# schematicamitfix.net
KiCad netlist of a schematic drawn in EAGLE
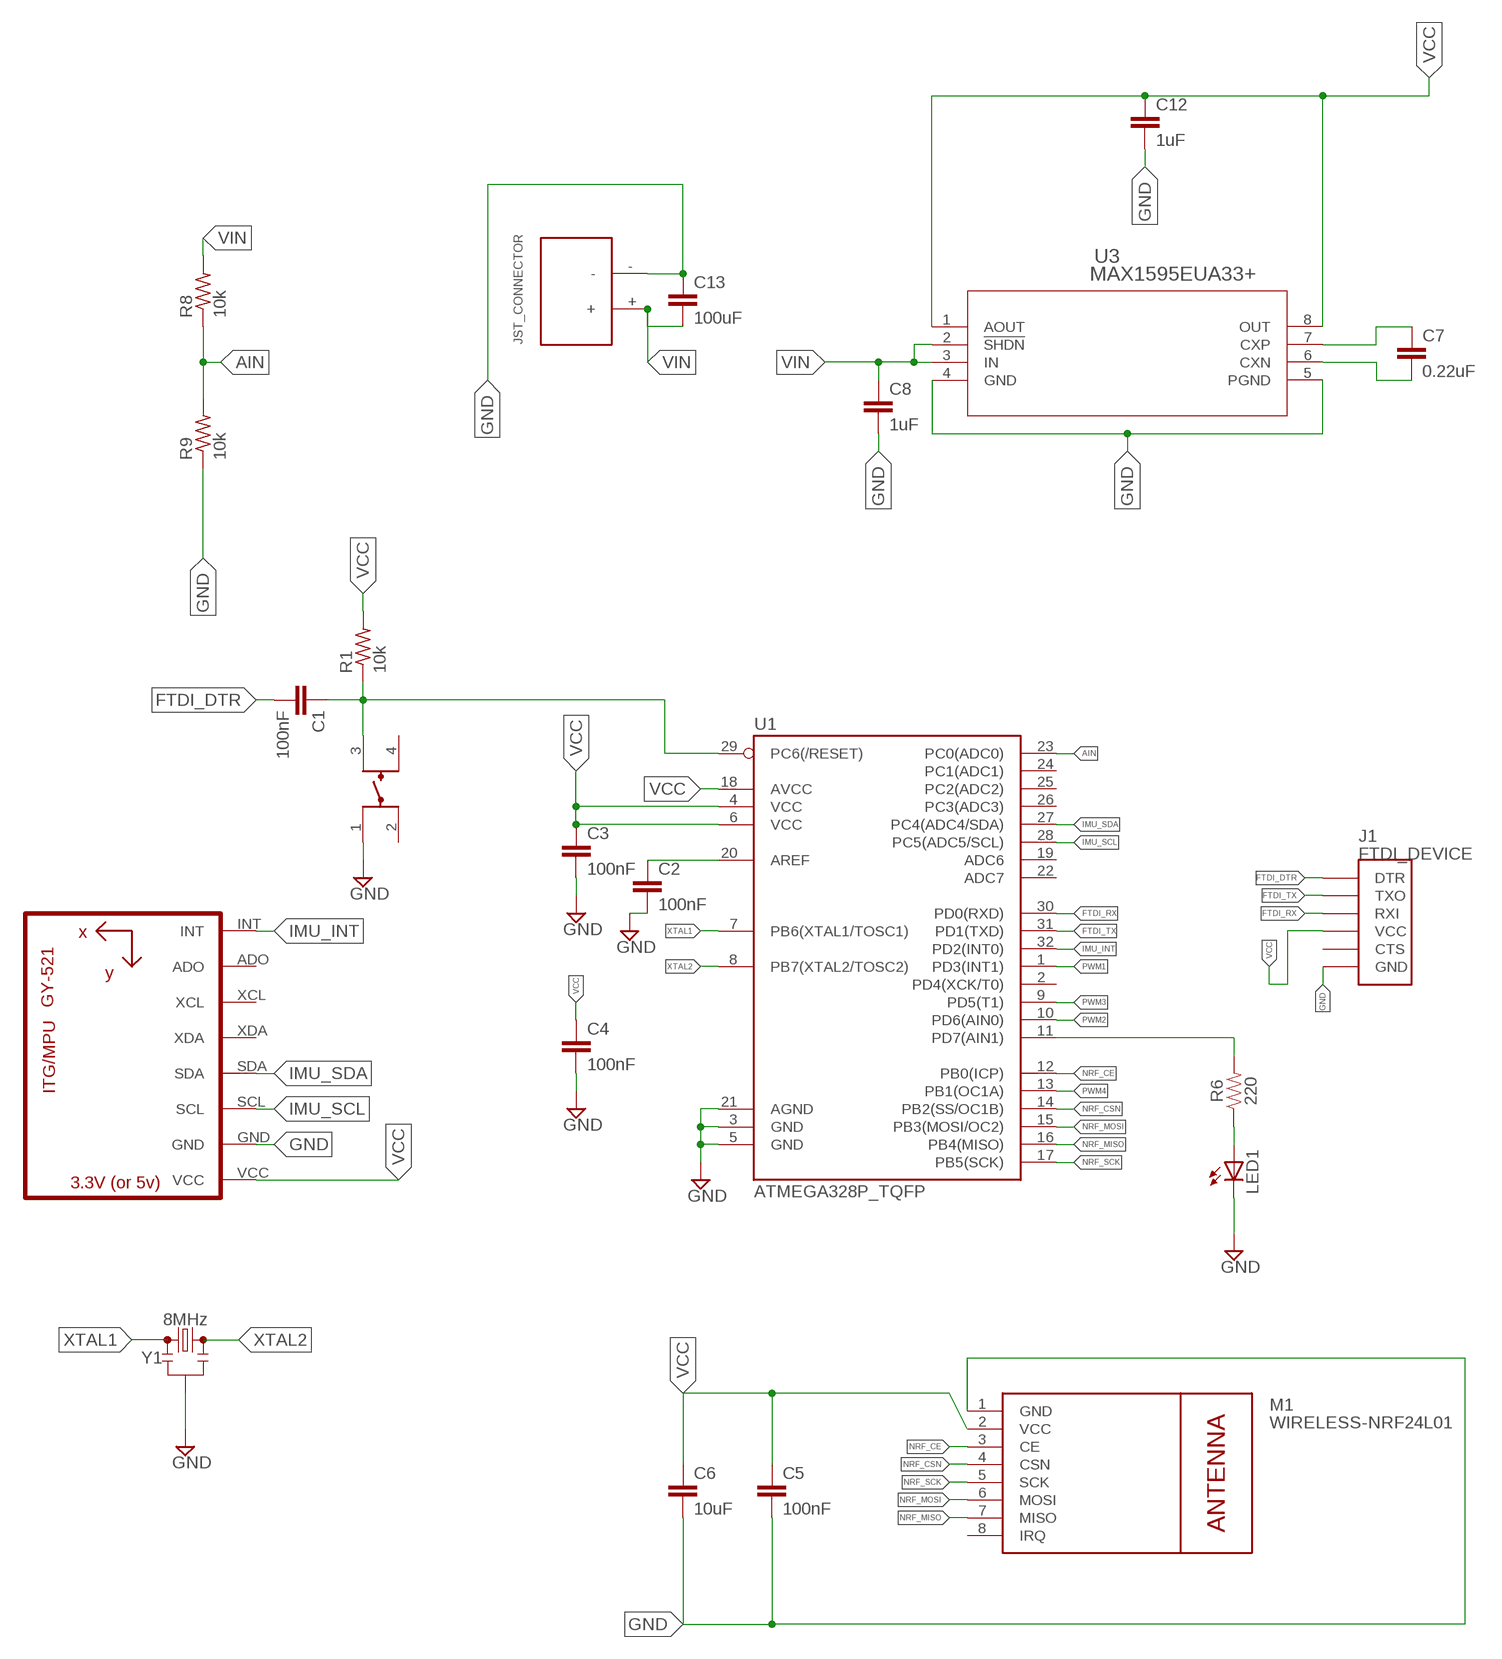
[diagram p0: schematic, sheet 1, part 1 of 3]
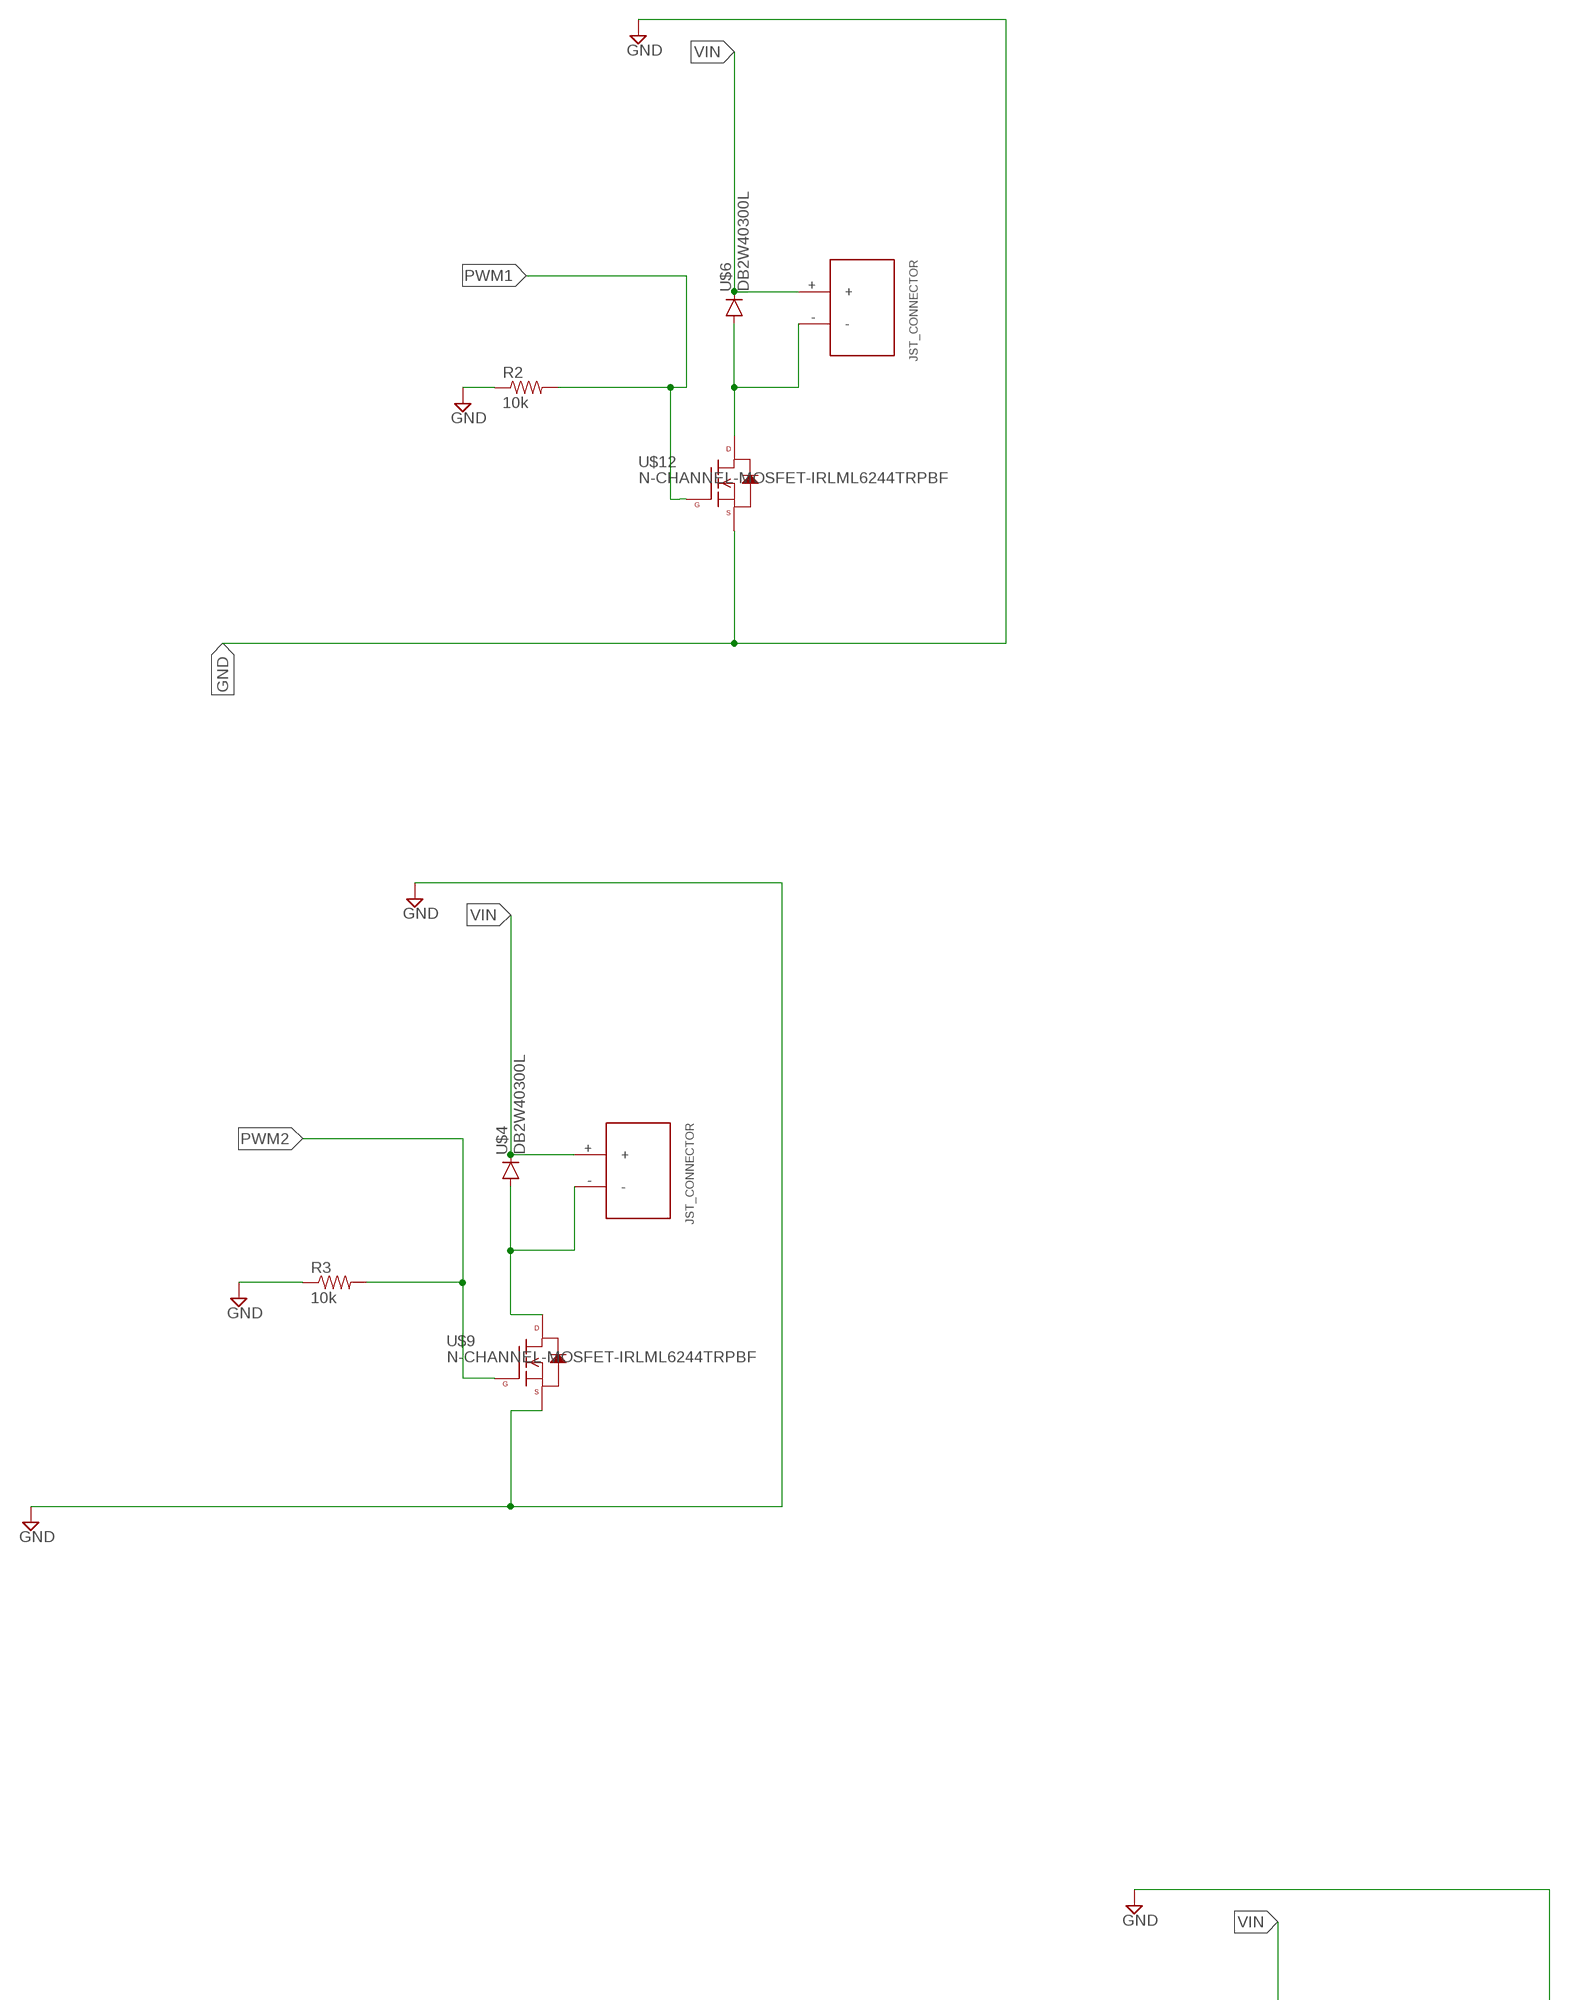
[diagram p1: schematic, sheet 1, part 2 of 3]
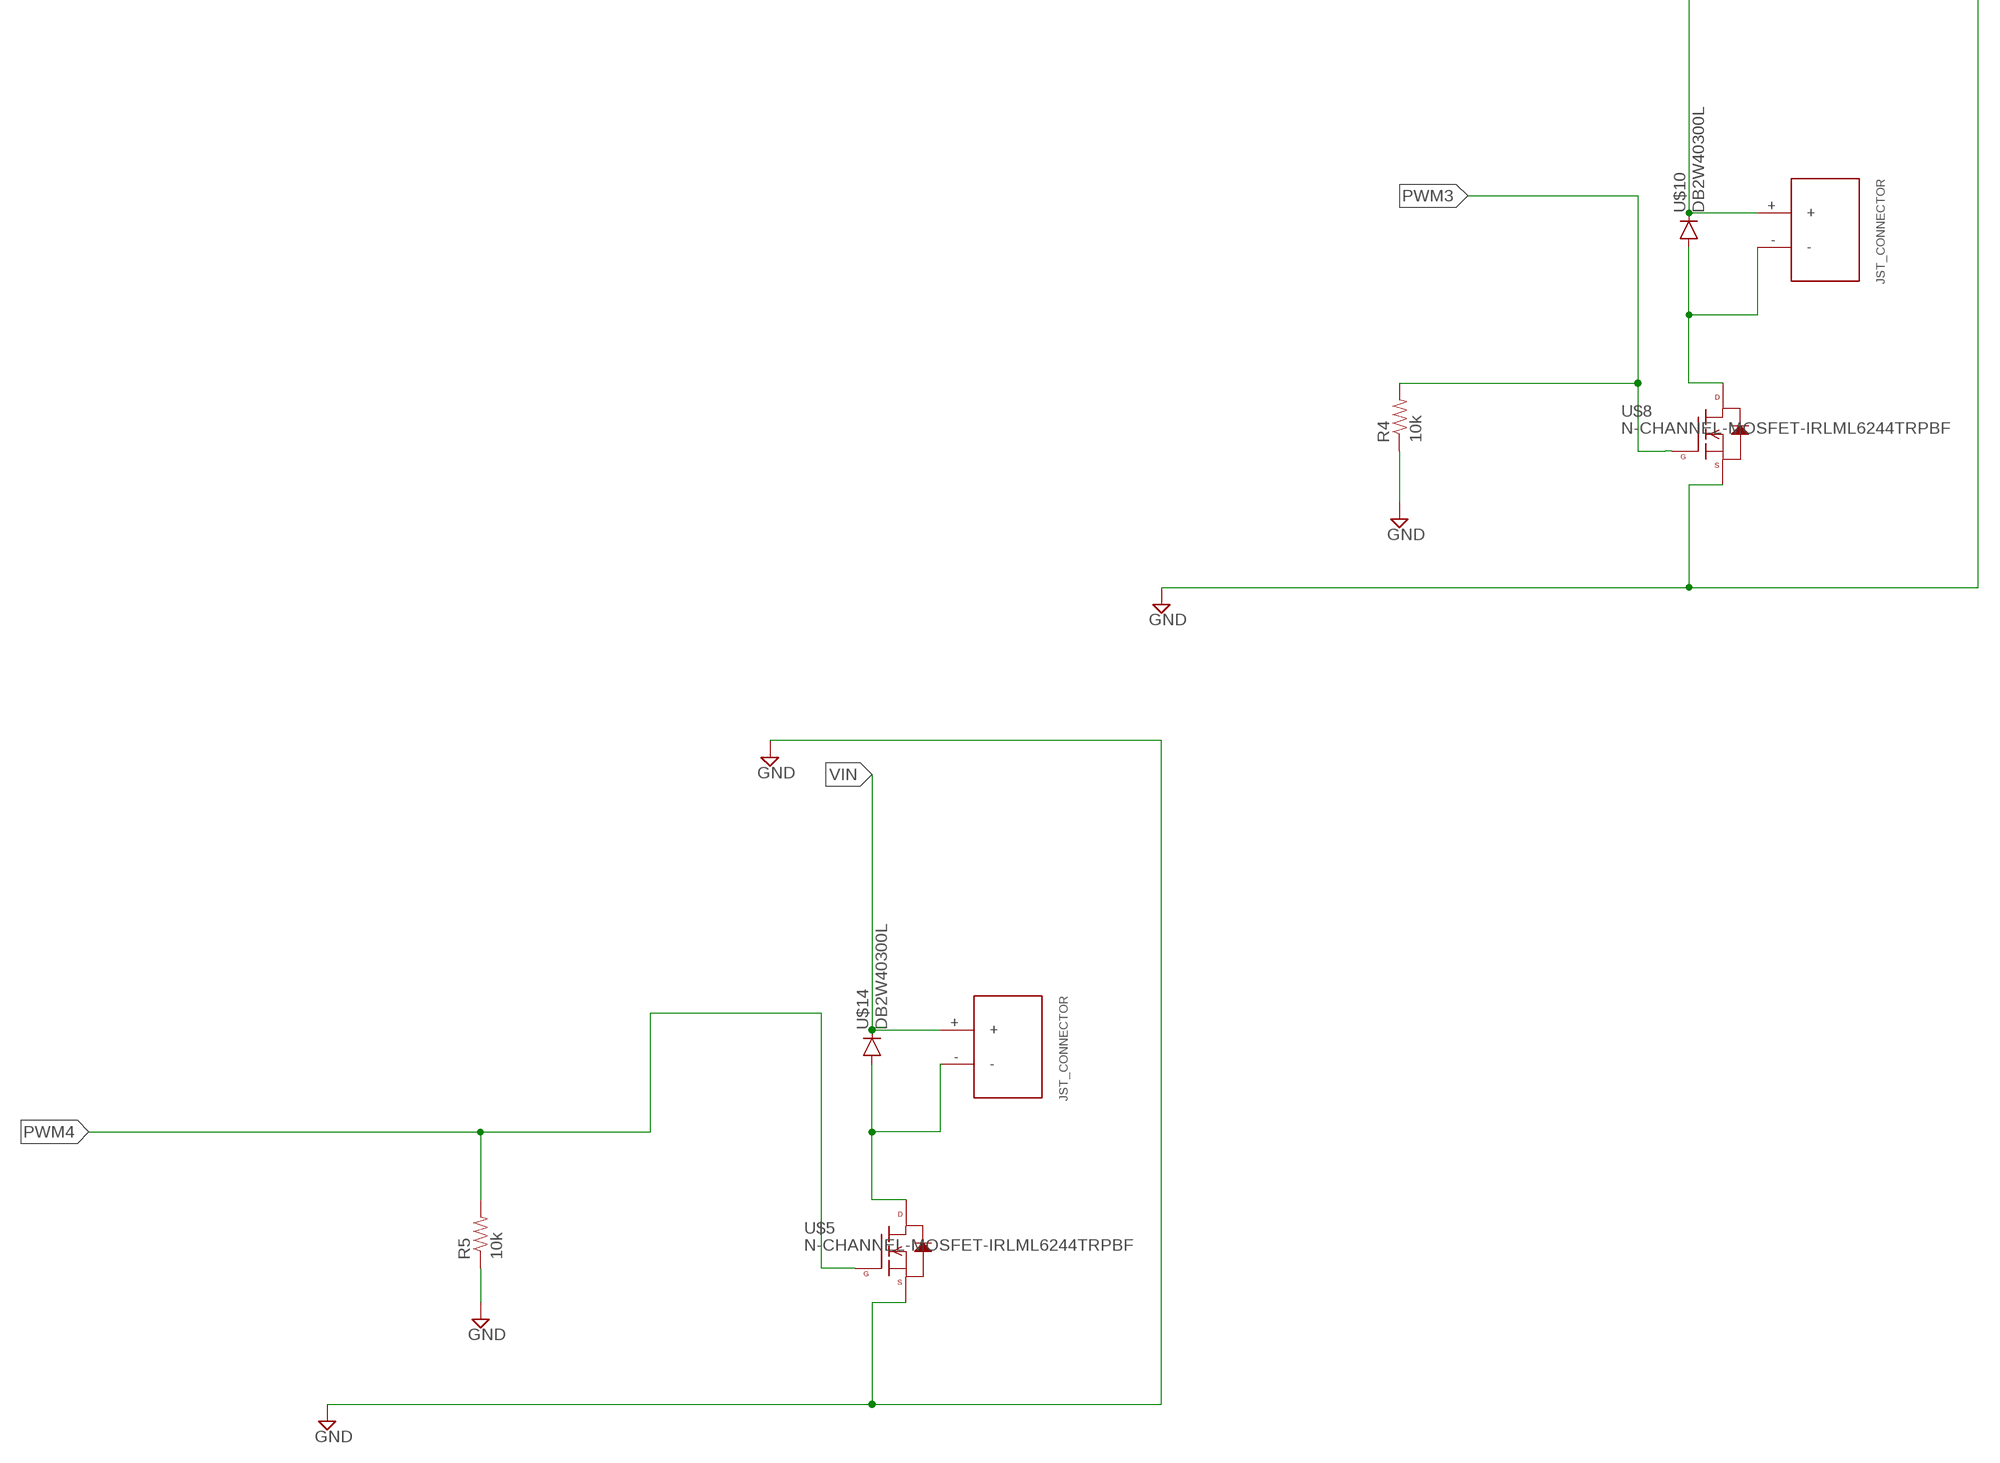
[diagram p2: schematic, sheet 1, part 3 of 3]

(export (version "E")
  (design (tool "Eeschema 10.0.6"))
  (components
    (comp (ref "C1")
      (value "100nF")
      (footprint "eagle-import:C0603")
      (libsource (lib "eagle-import") (part "C-EUC0603"))
    )
    (comp (ref "C2")
      (value "100nF")
      (footprint "eagle-import:C0603")
      (libsource (lib "eagle-import") (part "C-EUC0603"))
    )
    (comp (ref "C3")
      (value "100nF")
      (footprint "eagle-import:C0603")
      (libsource (lib "eagle-import") (part "C-EUC0603"))
    )
    (comp (ref "C4")
      (value "100nF")
      (footprint "eagle-import:C0603")
      (libsource (lib "eagle-import") (part "C-EUC0603"))
    )
    (comp (ref "C5")
      (value "100nF")
      (footprint "eagle-import:C0603")
      (libsource (lib "eagle-import") (part "C-EUC0603"))
    )
    (comp (ref "C6")
      (value "10uF")
      (footprint "eagle-import:C0603")
      (libsource (lib "eagle-import") (part "C-EUC0603"))
    )
    (comp (ref "C7")
      (value "0.22uF")
      (footprint "eagle-import:C0603")
      (libsource (lib "eagle-import") (part "C-EUC0603"))
    )
    (comp (ref "C8")
      (value "1uF")
      (footprint "eagle-import:C0805")
      (libsource (lib "eagle-import") (part "C-EUC0805"))
    )
    (comp (ref "C12")
      (value "1uF")
      (footprint "eagle-import:C0805")
      (libsource (lib "eagle-import") (part "C-EUC0805"))
    )
    (comp (ref "C13")
      (value "100uF")
      (footprint "eagle-import:C1210")
      (libsource (lib "eagle-import") (part "C-EUC1210"))
    )
    (comp (ref "J1")
      (value "FTDI_DEVICE")
      (footprint "eagle-import:FTDI_DEVICE_SIDE")
      (libsource (lib "eagle-import") (part "FTDI_DEVICE"))
    )
    (comp (ref "LED1")
      (value "LED1206")
      (footprint "eagle-import:LED-1206")
      (libsource (lib "eagle-import") (part "LED1206"))
    )
    (comp (ref "M1")
      (value "WIRELESS-NRF24L01")
      (footprint "eagle-import:WIRELESS-NRF24L01")
      (libsource (lib "eagle-import") (part "WIRELESS-NRF24L01"))
    )
    (comp (ref "R1")
      (value "10k")
      (footprint "eagle-import:R0603")
      (libsource (lib "eagle-import") (part "R-US_R0603"))
    )
    (comp (ref "R2")
      (value "10k")
      (footprint "eagle-import:0603-RES")
      (libsource (lib "eagle-import") (part "RESISTOR0603"))
    )
    (comp (ref "R3")
      (value "10k")
      (footprint "eagle-import:0603-RES")
      (libsource (lib "eagle-import") (part "RESISTOR0603"))
    )
    (comp (ref "R4")
      (value "10k")
      (footprint "eagle-import:0603-RES")
      (libsource (lib "eagle-import") (part "RESISTOR0603"))
    )
    (comp (ref "R5")
      (value "10k")
      (footprint "eagle-import:0603-RES")
      (libsource (lib "eagle-import") (part "RESISTOR0603"))
    )
    (comp (ref "R6")
      (value "220")
      (footprint "eagle-import:0603")
      (libsource (lib "eagle-import") (part "220OHM-0603-1/10W-1%"))
    )
    (comp (ref "R8")
      (value "10k")
      (footprint "eagle-import:R0603")
      (libsource (lib "eagle-import") (part "R-US_R0603"))
    )
    (comp (ref "R9")
      (value "10k")
      (footprint "eagle-import:R0603")
      (libsource (lib "eagle-import") (part "R-US_R0603"))
    )
    (comp (ref "U$1")
      (value "LL3301NF065QG")
      (footprint "eagle-import:LL3301NF065QG")
      (libsource (lib "eagle-import") (part "LL3301NF065QG"))
    )
    (comp (ref "U$3")
      (value "JST_CONNECTOR_FEMALE")
      (footprint "eagle-import:JST_CONNECTOR_FEMALE")
      (libsource (lib "eagle-import") (part "JST_CONNECTOR_FEMALE"))
    )
    (comp (ref "U$4")
      (value "DB2W40300L")
      (footprint "eagle-import:MINI2-F3-B")
      (libsource (lib "eagle-import") (part "DB2W40300L"))
    )
    (comp (ref "U$5")
      (value "N-CHANNEL-MOSFET-IRLML6244TRPBF")
      (footprint "eagle-import:SOT23-3")
      (libsource (lib "eagle-import") (part "N-CHANNEL-MOSFET-IRLML6244TRPBF"))
    )
    (comp (ref "U$6")
      (value "DB2W40300L")
      (footprint "eagle-import:MINI2-F3-B")
      (libsource (lib "eagle-import") (part "DB2W40300L"))
    )
    (comp (ref "U$7")
      (value "JST_CONNECTOR_FEMALE")
      (footprint "eagle-import:JST_CONNECTOR_FEMALE")
      (libsource (lib "eagle-import") (part "JST_CONNECTOR_FEMALE"))
    )
    (comp (ref "U$8")
      (value "N-CHANNEL-MOSFET-IRLML6244TRPBF")
      (footprint "eagle-import:SOT23-3")
      (libsource (lib "eagle-import") (part "N-CHANNEL-MOSFET-IRLML6244TRPBF"))
    )
    (comp (ref "U$9")
      (value "N-CHANNEL-MOSFET-IRLML6244TRPBF")
      (footprint "eagle-import:SOT23-3")
      (libsource (lib "eagle-import") (part "N-CHANNEL-MOSFET-IRLML6244TRPBF"))
    )
    (comp (ref "U$10")
      (value "DB2W40300L")
      (footprint "eagle-import:MINI2-F3-B")
      (libsource (lib "eagle-import") (part "DB2W40300L"))
    )
    (comp (ref "U$11")
      (value "JST_CONNECTOR_FEMALE")
      (footprint "eagle-import:JST_CONNECTOR_FEMALE")
      (libsource (lib "eagle-import") (part "JST_CONNECTOR_FEMALE"))
    )
    (comp (ref "U$12")
      (value "N-CHANNEL-MOSFET-IRLML6244TRPBF")
      (footprint "eagle-import:SOT23-3")
      (libsource (lib "eagle-import") (part "N-CHANNEL-MOSFET-IRLML6244TRPBF"))
    )
    (comp (ref "U$14")
      (value "DB2W40300L")
      (footprint "eagle-import:MINI2-F3-B")
      (libsource (lib "eagle-import") (part "DB2W40300L"))
    )
    (comp (ref "U$15")
      (value "JST_CONNECTOR_FEMALE")
      (footprint "eagle-import:JST_CONNECTOR_FEMALE")
      (libsource (lib "eagle-import") (part "JST_CONNECTOR_FEMALE"))
    )
    (comp (ref "U$19")
      (value "JST_CONNECTOR_FEMALE")
      (footprint "eagle-import:JST_CONNECTOR_FEMALE")
      (libsource (lib "eagle-import") (part "JST_CONNECTOR_FEMALE"))
    )
    (comp (ref "U1")
      (value "ATMEGA328P_TQFP")
      (footprint "eagle-import:TQFP32-08")
      (libsource (lib "eagle-import") (part "ATMEGA328P_TQFP"))
    )
    (comp (ref "U2")
      (value "GY-521MPU6050")
      (footprint "eagle-import:GY-521")
      (libsource (lib "eagle-import") (part "GY-521MPU6050"))
    )
    (comp (ref "U3")
      (value "MAX1595EUA33+")
      (footprint "eagle-import:21-0036K")
      (libsource (lib "eagle-import") (part "MAX1595EUA33+"))
    )
    (comp (ref "Y1")
      (value "8MHz")
      (footprint "eagle-import:RESONATOR-SMD-3.2X1.3")
      (libsource (lib "eagle-import") (part "RESONATOR-8MHZSMD_3.2X1.3"))
    )
  )
  (nets
    (net (code "1") (name "AIN") (class "Default")
      (node (ref "R8") (pin "1") (pinfunction "1_1") (pintype "passive"))
      (node (ref "R9") (pin "2") (pinfunction "2_2") (pintype "passive"))
      (node (ref "U1") (pin "23") (pinfunction "PC0(ADC0)_23") (pintype "bidirectional"))
    )
    (net (code "2") (name "FTDI_DTR") (class "Default")
      (node (ref "C1") (pin "2") (pinfunction "2_2") (pintype "passive"))
      (node (ref "J1") (pin "P$1") (pinfunction "DTR_P$1") (pintype "bidirectional"))
    )
    (net (code "3") (name "FTDI_RX") (class "Default")
      (node (ref "J1") (pin "P$3") (pinfunction "RXI_P$3") (pintype "bidirectional"))
      (node (ref "U1") (pin "30") (pinfunction "PD0(RXD)_30") (pintype "bidirectional"))
    )
    (net (code "4") (name "FTDI_TX") (class "Default")
      (node (ref "J1") (pin "P$2") (pinfunction "TXO_P$2") (pintype "bidirectional"))
      (node (ref "U1") (pin "31") (pinfunction "PD1(TXD)_31") (pintype "bidirectional"))
    )
    (net (code "5") (name "GND") (class "Default")
      (node (ref "C12") (pin "2") (pinfunction "2_2") (pintype "passive"))
      (node (ref "C13") (pin "1") (pinfunction "1_1") (pintype "passive"))
      (node (ref "C2") (pin "2") (pinfunction "2_2") (pintype "passive"))
      (node (ref "C3") (pin "2") (pinfunction "2_2") (pintype "passive"))
      (node (ref "C4") (pin "2") (pinfunction "2_2") (pintype "passive"))
      (node (ref "C5") (pin "2") (pinfunction "2_2") (pintype "passive"))
      (node (ref "C6") (pin "2") (pinfunction "2_2") (pintype "passive"))
      (node (ref "C8") (pin "2") (pinfunction "2_2") (pintype "passive"))
      (node (ref "J1") (pin "P$6") (pinfunction "GND_P$6") (pintype "bidirectional"))
      (node (ref "LED1") (pin "C") (pinfunction "C_C") (pintype "passive"))
      (node (ref "M1") (pin "1") (pinfunction "GND_1") (pintype "power_in"))
      (node (ref "R2") (pin "1") (pinfunction "1_1") (pintype "passive"))
      (node (ref "R3") (pin "1") (pinfunction "1_1") (pintype "passive"))
      (node (ref "R4") (pin "1") (pinfunction "1_1") (pintype "passive"))
      (node (ref "R5") (pin "1") (pinfunction "1_1") (pintype "passive"))
      (node (ref "R9") (pin "1") (pinfunction "1_1") (pintype "passive"))
      (node (ref "U$1") (pin "1") (pinfunction "1_1") (pintype "passive"))
      (node (ref "U$12") (pin "2") (pinfunction "S_2") (pintype "passive"))
      (node (ref "U$19") (pin "-") (pinfunction "-_-") (pintype "bidirectional"))
      (node (ref "U$5") (pin "2") (pinfunction "S_2") (pintype "passive"))
      (node (ref "U$8") (pin "2") (pinfunction "S_2") (pintype "passive"))
      (node (ref "U$9") (pin "2") (pinfunction "S_2") (pintype "passive"))
      (node (ref "U1") (pin "21") (pinfunction "AGND_21") (pintype "bidirectional"))
      (node (ref "U1") (pin "3") (pinfunction "GND_3") (pintype "bidirectional"))
      (node (ref "U1") (pin "5") (pinfunction "GND_5") (pintype "bidirectional"))
      (node (ref "U2") (pin "GND") (pinfunction "GND_GND") (pintype "bidirectional"))
      (node (ref "U3") (pin "4") (pinfunction "GND_4") (pintype "power_in"))
      (node (ref "U3") (pin "5") (pinfunction "PGND_5") (pintype "passive"))
      (node (ref "Y1") (pin "2") (pinfunction "2_2") (pintype "passive"))
    )
    (net (code "6") (name "IMU_INT") (class "Default")
      (node (ref "U1") (pin "32") (pinfunction "PD2(INT0)_32") (pintype "bidirectional"))
      (node (ref "U2") (pin "INT") (pinfunction "INT_INT") (pintype "bidirectional"))
    )
    (net (code "7") (name "IMU_SCL") (class "Default")
      (node (ref "U1") (pin "28") (pinfunction "PC5(ADC5/SCL)_28") (pintype "bidirectional"))
      (node (ref "U2") (pin "SCL") (pinfunction "SCL_SCL") (pintype "bidirectional"))
    )
    (net (code "8") (name "IMU_SDA") (class "Default")
      (node (ref "U1") (pin "27") (pinfunction "PC4(ADC4/SDA)_27") (pintype "bidirectional"))
      (node (ref "U2") (pin "SDA") (pinfunction "SDA_SDA") (pintype "bidirectional"))
    )
    (net (code "9") (name "NRF_CE") (class "Default")
      (node (ref "M1") (pin "3") (pinfunction "CE_3") (pintype "bidirectional"))
      (node (ref "U1") (pin "12") (pinfunction "PB0(ICP)_12") (pintype "bidirectional"))
    )
    (net (code "10") (name "NRF_CSN") (class "Default")
      (node (ref "M1") (pin "4") (pinfunction "CSN_4") (pintype "bidirectional"))
      (node (ref "U1") (pin "14") (pinfunction "PB2(SS/OC1B)_14") (pintype "bidirectional"))
    )
    (net (code "11") (name "NRF_MISO") (class "Default")
      (node (ref "M1") (pin "7") (pinfunction "MISO_7") (pintype "bidirectional"))
      (node (ref "U1") (pin "16") (pinfunction "PB4(MISO)_16") (pintype "bidirectional"))
    )
    (net (code "12") (name "NRF_MOSI") (class "Default")
      (node (ref "M1") (pin "6") (pinfunction "MOSI_6") (pintype "bidirectional"))
      (node (ref "U1") (pin "15") (pinfunction "PB3(MOSI/OC2)_15") (pintype "bidirectional"))
    )
    (net (code "13") (name "NRF_SCK") (class "Default")
      (node (ref "M1") (pin "5") (pinfunction "SCK_5") (pintype "bidirectional"))
      (node (ref "U1") (pin "17") (pinfunction "PB5(SCK)_17") (pintype "bidirectional"))
    )
    (net (code "14") (name "Net-(LED1-PadA)") (class "Default")
      (node (ref "LED1") (pin "A") (pinfunction "A_A") (pintype "passive"))
      (node (ref "R6") (pin "1") (pinfunction "1_1") (pintype "passive"))
    )
    (net (code "15") (name "Net-(U$4-PPIN)") (class "Default")
      (node (ref "U$3") (pin "-") (pinfunction "-_-") (pintype "bidirectional"))
      (node (ref "U$4") (pin "POS") (pinfunction "PPIN_POS") (pintype "passive"))
      (node (ref "U$9") (pin "3") (pinfunction "D_3") (pintype "passive"))
    )
    (net (code "16") (name "Net-(U$10-PPIN)") (class "Default")
      (node (ref "U$10") (pin "POS") (pinfunction "PPIN_POS") (pintype "passive"))
      (node (ref "U$11") (pin "-") (pinfunction "-_-") (pintype "bidirectional"))
      (node (ref "U$8") (pin "3") (pinfunction "D_3") (pintype "passive"))
    )
    (net (code "17") (name "Net-(U$12-D)") (class "Default")
      (node (ref "U$12") (pin "3") (pinfunction "D_3") (pintype "passive"))
      (node (ref "U$6") (pin "POS") (pinfunction "PPIN_POS") (pintype "passive"))
      (node (ref "U$7") (pin "-") (pinfunction "-_-") (pintype "bidirectional"))
    )
    (net (code "18") (name "Net-(U$14-PPIN)") (class "Default")
      (node (ref "U$14") (pin "POS") (pinfunction "PPIN_POS") (pintype "passive"))
      (node (ref "U$15") (pin "-") (pinfunction "-_-") (pintype "bidirectional"))
      (node (ref "U$5") (pin "3") (pinfunction "D_3") (pintype "passive"))
    )
    (net (code "19") (name "Net-(U1-AREF)") (class "Default")
      (node (ref "C2") (pin "1") (pinfunction "1_1") (pintype "passive"))
      (node (ref "U1") (pin "20") (pinfunction "AREF_20") (pintype "bidirectional"))
    )
    (net (code "20") (name "Net-(U1-PC6({slash}RESET))") (class "Default")
      (node (ref "C1") (pin "1") (pinfunction "1_1") (pintype "passive"))
      (node (ref "R1") (pin "1") (pinfunction "1_1") (pintype "passive"))
      (node (ref "U$1") (pin "3") (pinfunction "3_3") (pintype "passive"))
      (node (ref "U1") (pin "29") (pinfunction "PC6(/RESET)_29") (pintype "bidirectional"))
    )
    (net (code "21") (name "Net-(U1-PD7(AIN1))") (class "Default")
      (node (ref "R6") (pin "2") (pinfunction "2_2") (pintype "passive"))
      (node (ref "U1") (pin "11") (pinfunction "PD7(AIN1)_11") (pintype "bidirectional"))
    )
    (net (code "22") (name "Net-(U3-CXN)") (class "Default")
      (node (ref "C7") (pin "2") (pinfunction "2_2") (pintype "passive"))
      (node (ref "U3") (pin "6") (pinfunction "CXN_6") (pintype "passive"))
    )
    (net (code "23") (name "Net-(U3-CXP)") (class "Default")
      (node (ref "C7") (pin "1") (pinfunction "1_1") (pintype "passive"))
      (node (ref "U3") (pin "7") (pinfunction "CXP_7") (pintype "passive"))
    )
    (net (code "24") (name "PWM1") (class "Default")
      (node (ref "R2") (pin "2") (pinfunction "2_2") (pintype "passive"))
      (node (ref "U$12") (pin "1") (pinfunction "G_1") (pintype "passive"))
      (node (ref "U1") (pin "1") (pinfunction "PD3(INT1)_1") (pintype "bidirectional"))
    )
    (net (code "25") (name "PWM2") (class "Default")
      (node (ref "R3") (pin "2") (pinfunction "2_2") (pintype "passive"))
      (node (ref "U$9") (pin "1") (pinfunction "G_1") (pintype "passive"))
      (node (ref "U1") (pin "10") (pinfunction "PD6(AIN0)_10") (pintype "bidirectional"))
    )
    (net (code "26") (name "PWM3") (class "Default")
      (node (ref "R4") (pin "2") (pinfunction "2_2") (pintype "passive"))
      (node (ref "U$8") (pin "1") (pinfunction "G_1") (pintype "passive"))
      (node (ref "U1") (pin "9") (pinfunction "PD5(T1)_9") (pintype "bidirectional"))
    )
    (net (code "27") (name "PWM4") (class "Default")
      (node (ref "R5") (pin "2") (pinfunction "2_2") (pintype "passive"))
      (node (ref "U$5") (pin "1") (pinfunction "G_1") (pintype "passive"))
      (node (ref "U1") (pin "13") (pinfunction "PB1(OC1A)_13") (pintype "bidirectional"))
    )
    (net (code "28") (name "VCC") (class "Default")
      (node (ref "C12") (pin "1") (pinfunction "1_1") (pintype "passive"))
      (node (ref "C3") (pin "1") (pinfunction "1_1") (pintype "passive"))
      (node (ref "C4") (pin "1") (pinfunction "1_1") (pintype "passive"))
      (node (ref "C5") (pin "1") (pinfunction "1_1") (pintype "passive"))
      (node (ref "C6") (pin "1") (pinfunction "1_1") (pintype "passive"))
      (node (ref "J1") (pin "P$4") (pinfunction "VCC_P$4") (pintype "bidirectional"))
      (node (ref "M1") (pin "2") (pinfunction "VCC_2") (pintype "power_in"))
      (node (ref "R1") (pin "2") (pinfunction "2_2") (pintype "passive"))
      (node (ref "U1") (pin "18") (pinfunction "AVCC_18") (pintype "bidirectional"))
      (node (ref "U1") (pin "4") (pinfunction "VCC_4") (pintype "bidirectional"))
      (node (ref "U1") (pin "6") (pinfunction "VCC_6") (pintype "bidirectional"))
      (node (ref "U2") (pin "VCC") (pinfunction "VCC_VCC") (pintype "bidirectional"))
      (node (ref "U3") (pin "1") (pinfunction "AOUT_1") (pintype "passive"))
      (node (ref "U3") (pin "8") (pinfunction "OUT_8") (pintype "passive"))
    )
    (net (code "29") (name "VIN") (class "Default")
      (node (ref "C13") (pin "2") (pinfunction "2_2") (pintype "passive"))
      (node (ref "C8") (pin "1") (pinfunction "1_1") (pintype "passive"))
      (node (ref "R8") (pin "2") (pinfunction "2_2") (pintype "passive"))
      (node (ref "U$10") (pin "NEG") (pinfunction "GPIN_NEG") (pintype "passive"))
      (node (ref "U$11") (pin "+") (pinfunction "+_+") (pintype "bidirectional"))
      (node (ref "U$14") (pin "NEG") (pinfunction "GPIN_NEG") (pintype "passive"))
      (node (ref "U$15") (pin "+") (pinfunction "+_+") (pintype "bidirectional"))
      (node (ref "U$19") (pin "+") (pinfunction "+_+") (pintype "bidirectional"))
      (node (ref "U$3") (pin "+") (pinfunction "+_+") (pintype "bidirectional"))
      (node (ref "U$4") (pin "NEG") (pinfunction "GPIN_NEG") (pintype "passive"))
      (node (ref "U$6") (pin "NEG") (pinfunction "GPIN_NEG") (pintype "passive"))
      (node (ref "U$7") (pin "+") (pinfunction "+_+") (pintype "bidirectional"))
      (node (ref "U3") (pin "2") (pinfunction "~{SHDN}_2") (pintype "passive"))
      (node (ref "U3") (pin "3") (pinfunction "IN_3") (pintype "input"))
    )
    (net (code "30") (name "XTAL1") (class "Default")
      (node (ref "U1") (pin "7") (pinfunction "PB6(XTAL1/TOSC1)_7") (pintype "bidirectional"))
      (node (ref "Y1") (pin "1") (pinfunction "1_1") (pintype "passive"))
    )
    (net (code "31") (name "XTAL2") (class "Default")
      (node (ref "U1") (pin "8") (pinfunction "PB7(XTAL2/TOSC2)_8") (pintype "bidirectional"))
      (node (ref "Y1") (pin "3") (pinfunction "3_3") (pintype "passive"))
    )
    (net (code "32") (name "unconnected-(J1-CTS-PadP$5)") (class "Default")
      (node (ref "J1") (pin "P$5") (pinfunction "CTS_P$5") (pintype "bidirectional"))
    )
    (net (code "33") (name "unconnected-(M1-IRQ-Pad8)") (class "Default")
      (node (ref "M1") (pin "8") (pinfunction "IRQ_8") (pintype "bidirectional"))
    )
    (net (code "34") (name "unconnected-(U$1-Pad2)") (class "Default")
      (node (ref "U$1") (pin "2") (pinfunction "2_2") (pintype "passive"))
    )
    (net (code "35") (name "unconnected-(U$1-Pad4)") (class "Default")
      (node (ref "U$1") (pin "4") (pinfunction "4_4") (pintype "passive"))
    )
    (net (code "36") (name "unconnected-(U1-ADC6-Pad19)") (class "Default")
      (node (ref "U1") (pin "19") (pinfunction "ADC6_19") (pintype "bidirectional"))
    )
    (net (code "37") (name "unconnected-(U1-ADC7-Pad22)") (class "Default")
      (node (ref "U1") (pin "22") (pinfunction "ADC7_22") (pintype "bidirectional"))
    )
    (net (code "38") (name "unconnected-(U1-PC1(ADC1)-Pad24)") (class "Default")
      (node (ref "U1") (pin "24") (pinfunction "PC1(ADC1)_24") (pintype "bidirectional"))
    )
    (net (code "39") (name "unconnected-(U1-PC2(ADC2)-Pad25)") (class "Default")
      (node (ref "U1") (pin "25") (pinfunction "PC2(ADC2)_25") (pintype "bidirectional"))
    )
    (net (code "40") (name "unconnected-(U1-PC3(ADC3)-Pad26)") (class "Default")
      (node (ref "U1") (pin "26") (pinfunction "PC3(ADC3)_26") (pintype "bidirectional"))
    )
    (net (code "41") (name "unconnected-(U1-PD4(XCK{slash}T0)-Pad2)") (class "Default")
      (node (ref "U1") (pin "2") (pinfunction "PD4(XCK/T0)_2") (pintype "bidirectional"))
    )
    (net (code "42") (name "unconnected-(U2-PadADO)") (class "Default")
      (node (ref "U2") (pin "ADO") (pinfunction "ADO_ADO") (pintype "bidirectional"))
    )
    (net (code "43") (name "unconnected-(U2-PadXCL)") (class "Default")
      (node (ref "U2") (pin "XCL") (pinfunction "XCL_XCL") (pintype "bidirectional"))
    )
    (net (code "44") (name "unconnected-(U2-PadXDA)") (class "Default")
      (node (ref "U2") (pin "XDA") (pinfunction "XDA_XDA") (pintype "bidirectional"))
    )
  )
)
